# IntegroDiferencial_SCH.net
KiCad netlist of a schematic drawn in Altium Designer
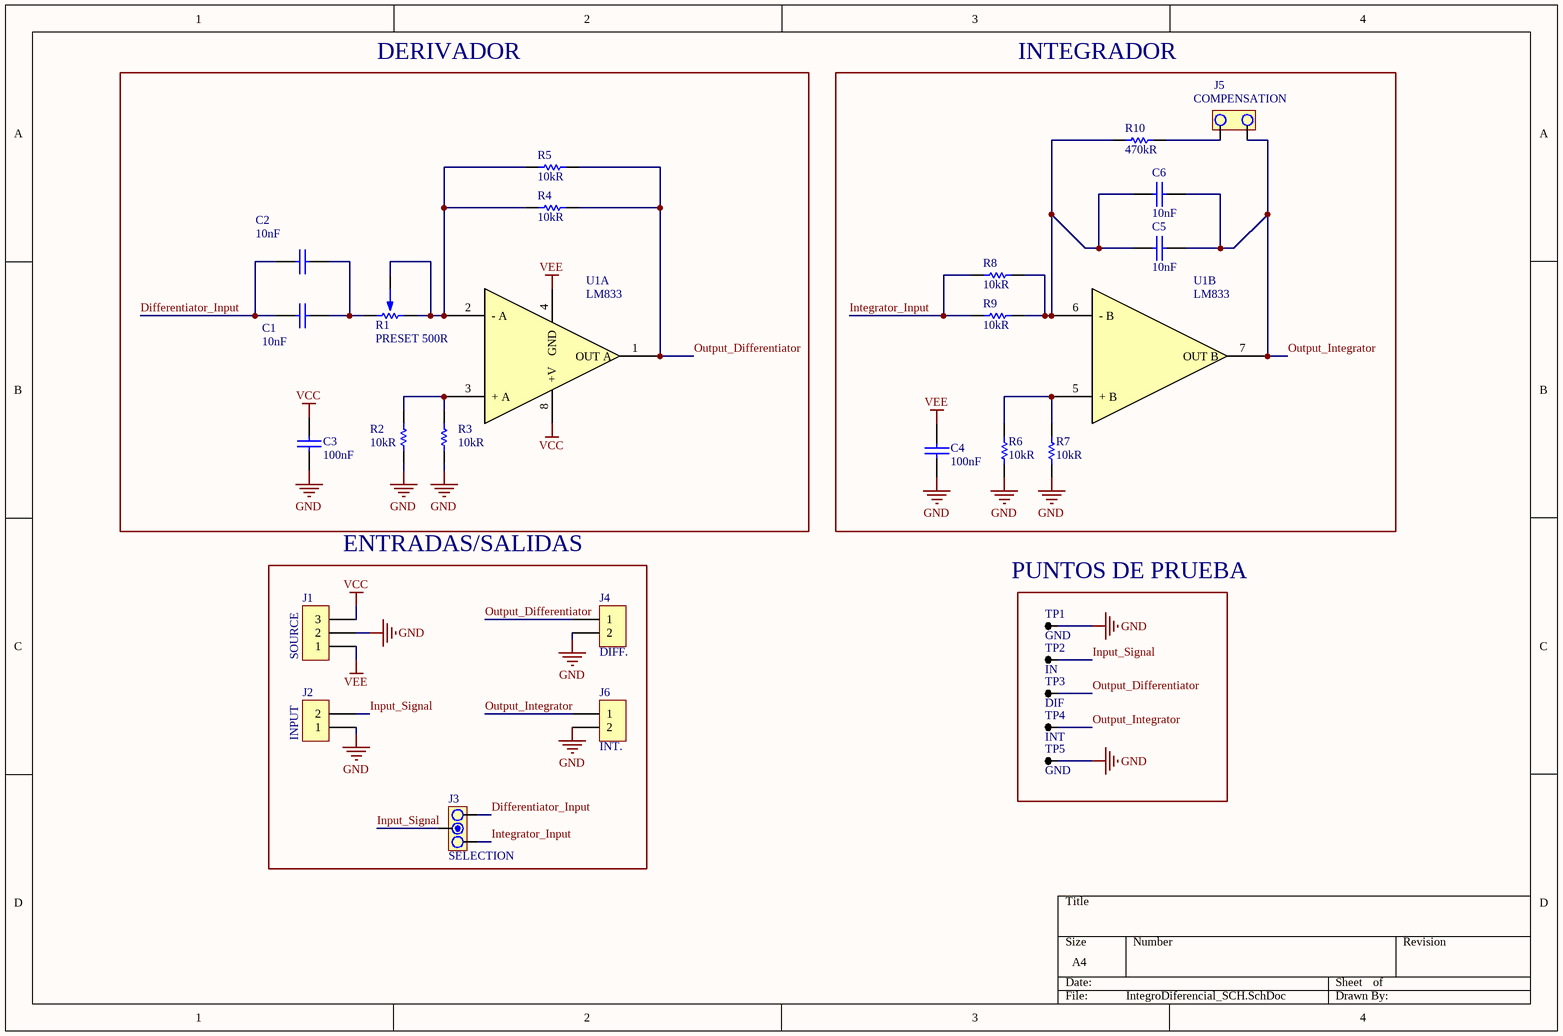
[diagram p0: IntegroDiferencial_SCH.SchDoc]

(export (version "E")
  (design (tool "Eeschema 10.0.6"))
  (components
    (comp (ref "C1")
      (value "10nF")
      (footprint "0805")
      (description "CAP 10nF 0805")
      (libsource (lib "LIBEBAL") (part "CAP"))
    )
    (comp (ref "C2")
      (value "10nF")
      (footprint "0805")
      (description "CAP 10nF 0805")
      (libsource (lib "LIBEBAL") (part "CAP"))
    )
    (comp (ref "C3")
      (value "100nF")
      (footprint "0805")
      (description "CAP 100nF 0805")
      (libsource (lib "LIBEBAL") (part "CAP"))
    )
    (comp (ref "C4")
      (value "100nF")
      (footprint "0805")
      (description "CAP 100nF 0805")
      (libsource (lib "LIBEBAL") (part "CAP"))
    )
    (comp (ref "C5")
      (value "10nF")
      (footprint "0805")
      (description "CAP 10nF 0805")
      (libsource (lib "LIBEBAL") (part "CAP"))
    )
    (comp (ref "C6")
      (value "10nF")
      (footprint "0805")
      (description "CAP 10nF 0805")
      (libsource (lib "LIBEBAL") (part "CAP"))
    )
    (comp (ref "J1")
      (value "SOURCE")
      (footprint "BORNERA3")
      (description "BORNERA 3")
      (libsource (lib "LIBEBAL") (part "BORNERA 3"))
    )
    (comp (ref "J2")
      (value "INPUT")
      (footprint "BORNERA2")
      (description "BORNERA 2")
      (libsource (lib "LIBEBAL") (part "BORNERA 2"))
    )
    (comp (ref "J3")
      (value "SELECTION")
      (footprint "JUMPER3")
      (description "JUMPER")
      (libsource (lib "LIBEBAL") (part "JUMPER3"))
    )
    (comp (ref "J4")
      (value "DIFF.")
      (footprint "BORNERA2")
      (description "BORNERA 2")
      (libsource (lib "") (part "BORNERA 2_1"))
    )
    (comp (ref "J5")
      (value "COMPENSATION")
      (footprint "JUMPER2")
      (description "JUMPER")
      (libsource (lib "LIBEBAL") (part "JUMPER"))
    )
    (comp (ref "J6")
      (value "INT.")
      (footprint "BORNERA2")
      (description "BORNERA 2")
      (libsource (lib "") (part "BORNERA 2_1"))
    )
    (comp (ref "R1") (value "PRESET 500R") (footprint "PRESET V") (libsource (lib "LIBEBAL") (part "PRESET")))
    (comp (ref "R2")
      (value "10kR")
      (footprint "0805")
      (description "RES 10kR 0805")
      (libsource (lib "LIBEBAL") (part "RES"))
    )
    (comp (ref "R3")
      (value "10kR")
      (footprint "0805")
      (description "RES 10kR 0805")
      (libsource (lib "LIBEBAL") (part "RES"))
    )
    (comp (ref "R4")
      (value "10kR")
      (footprint "0805")
      (description "RES 10kR 0805")
      (libsource (lib "LIBEBAL") (part "RES"))
    )
    (comp (ref "R5")
      (value "10kR")
      (footprint "0805")
      (description "RES 10kR 0805")
      (libsource (lib "LIBEBAL") (part "RES"))
    )
    (comp (ref "R6")
      (value "10kR")
      (footprint "0805")
      (description "RES 10kR 0805")
      (libsource (lib "LIBEBAL") (part "RES"))
    )
    (comp (ref "R7")
      (value "10kR")
      (footprint "0805")
      (description "RES 10kR 0805")
      (libsource (lib "LIBEBAL") (part "RES"))
    )
    (comp (ref "R8")
      (value "10kR")
      (footprint "0805")
      (description "RES 10kR 0805")
      (libsource (lib "LIBEBAL") (part "RES"))
    )
    (comp (ref "R9")
      (value "10kR")
      (footprint "0805")
      (description "RES 10kR 0805")
      (libsource (lib "LIBEBAL") (part "RES"))
    )
    (comp (ref "R10")
      (value "470kR")
      (footprint "0805")
      (description "RES 470kR 0805")
      (libsource (lib "LIBEBAL") (part "RES"))
    )
    (comp (ref "TP1")
      (value "GND")
      (footprint "TPTH")
      (description "TESTPOINT")
      (libsource (lib "LIBEBAL") (part "TP"))
    )
    (comp (ref "TP2")
      (value "IN")
      (footprint "TPTH")
      (description "TESTPOINT")
      (libsource (lib "LIBEBAL") (part "TP"))
    )
    (comp (ref "TP3")
      (value "DIF")
      (footprint "TPTH")
      (description "TESTPOINT")
      (libsource (lib "LIBEBAL") (part "TP"))
    )
    (comp (ref "TP4")
      (value "INT")
      (footprint "TPTH")
      (description "TESTPOINT")
      (libsource (lib "LIBEBAL") (part "TP"))
    )
    (comp (ref "TP5")
      (value "GND")
      (footprint "TPTH")
      (description "TESTPOINT")
      (libsource (lib "LIBEBAL") (part "TP"))
    )
    (comp (ref "U1")
      (value "LM833")
      (footprint "DIP8")
      (description "Dual Audio Operational Amplifier")
      (libsource (lib "LIBEBAL") (part "LM833"))
    )
  )
  (nets
    (net (code "1") (name "/Differentiator_Input") (class "Default")
      (node (ref "C1") (pin "1") (pinfunction "1_1") (pintype "passive"))
      (node (ref "C2") (pin "1") (pinfunction "1_1") (pintype "passive"))
      (node (ref "J3") (pin "1") (pinfunction "1_1") (pintype "passive"))
    )
    (net (code "2") (name "/Input_Signal") (class "Default")
      (node (ref "J2") (pin "2") (pinfunction "2_2") (pintype "passive"))
      (node (ref "J3") (pin "2") (pinfunction "2_2") (pintype "passive"))
      (node (ref "TP2") (pin "1") (pinfunction "1_1") (pintype "passive"))
    )
    (net (code "3") (name "/Integrator_Input") (class "Default")
      (node (ref "J3") (pin "3") (pinfunction "3_3") (pintype "passive"))
      (node (ref "R8") (pin "1") (pinfunction "1_1") (pintype "passive"))
      (node (ref "R9") (pin "1") (pinfunction "1_1") (pintype "passive"))
    )
    (net (code "4") (name "/Output_Differentiator") (class "Default")
      (node (ref "J4") (pin "1") (pinfunction "1_1") (pintype "passive"))
      (node (ref "R4") (pin "1") (pinfunction "1_1") (pintype "passive"))
      (node (ref "R5") (pin "1") (pinfunction "1_1") (pintype "passive"))
      (node (ref "TP3") (pin "1") (pinfunction "1_1") (pintype "passive"))
      (node (ref "U1") (pin "1") (pinfunction "OUT_A_1") (pintype "passive"))
    )
    (net (code "5") (name "/Output_Integrator") (class "Default")
      (node (ref "C5") (pin "1") (pinfunction "1_1") (pintype "passive"))
      (node (ref "C6") (pin "1") (pinfunction "1_1") (pintype "passive"))
      (node (ref "J5") (pin "1") (pinfunction "1_1") (pintype "passive"))
      (node (ref "J6") (pin "1") (pinfunction "1_1") (pintype "passive"))
      (node (ref "TP4") (pin "1") (pinfunction "1_1") (pintype "passive"))
      (node (ref "U1") (pin "7") (pinfunction "OUT_B_7") (pintype "passive"))
    )
    (net (code "6") (name "GND") (class "Default")
      (node (ref "C3") (pin "1") (pinfunction "1_1") (pintype "passive"))
      (node (ref "C4") (pin "1") (pinfunction "1_1") (pintype "passive"))
      (node (ref "J1") (pin "2") (pinfunction "2_2") (pintype "passive"))
      (node (ref "J2") (pin "1") (pinfunction "1_1") (pintype "passive"))
      (node (ref "J4") (pin "2") (pinfunction "2_2") (pintype "passive"))
      (node (ref "J6") (pin "2") (pinfunction "2_2") (pintype "passive"))
      (node (ref "R2") (pin "1") (pinfunction "1_1") (pintype "passive"))
      (node (ref "R3") (pin "1") (pinfunction "1_1") (pintype "passive"))
      (node (ref "R6") (pin "1") (pinfunction "1_1") (pintype "passive"))
      (node (ref "R7") (pin "1") (pinfunction "1_1") (pintype "passive"))
      (node (ref "TP1") (pin "1") (pinfunction "1_1") (pintype "passive"))
      (node (ref "TP5") (pin "1") (pinfunction "1_1") (pintype "passive"))
    )
    (net (code "7") (name "Net-(C1-Pad2)") (class "Default")
      (node (ref "C1") (pin "2") (pinfunction "2_2") (pintype "passive"))
      (node (ref "C2") (pin "2") (pinfunction "2_2") (pintype "passive"))
      (node (ref "R1") (pin "1") (pinfunction "1_1") (pintype "passive"))
    )
    (net (code "8") (name "Net-(J5-Pad2)") (class "Default")
      (node (ref "J5") (pin "2") (pinfunction "2_2") (pintype "passive"))
      (node (ref "R10") (pin "2") (pinfunction "2_2") (pintype "passive"))
    )
    (net (code "9") (name "Net-(U1A-+_A)") (class "Default")
      (node (ref "R2") (pin "2") (pinfunction "2_2") (pintype "passive"))
      (node (ref "R3") (pin "2") (pinfunction "2_2") (pintype "passive"))
      (node (ref "U1") (pin "3") (pinfunction "+_A_3") (pintype "passive"))
    )
    (net (code "10") (name "Net-(U1A--_A)") (class "Default")
      (node (ref "R1") (pin "2") (pinfunction "2_2") (pintype "passive"))
      (node (ref "R1") (pin "3") (pinfunction "3_3") (pintype "passive"))
      (node (ref "R4") (pin "2") (pinfunction "2_2") (pintype "passive"))
      (node (ref "R5") (pin "2") (pinfunction "2_2") (pintype "passive"))
      (node (ref "U1") (pin "2") (pinfunction "-_A_2") (pintype "passive"))
    )
    (net (code "11") (name "Net-(U1B-+_B)") (class "Default")
      (node (ref "R6") (pin "2") (pinfunction "2_2") (pintype "passive"))
      (node (ref "R7") (pin "2") (pinfunction "2_2") (pintype "passive"))
      (node (ref "U1") (pin "5") (pinfunction "+_B_5") (pintype "passive"))
    )
    (net (code "12") (name "Net-(U1B--_B)") (class "Default")
      (node (ref "C5") (pin "2") (pinfunction "2_2") (pintype "passive"))
      (node (ref "C6") (pin "2") (pinfunction "2_2") (pintype "passive"))
      (node (ref "R10") (pin "1") (pinfunction "1_1") (pintype "passive"))
      (node (ref "R8") (pin "2") (pinfunction "2_2") (pintype "passive"))
      (node (ref "R9") (pin "2") (pinfunction "2_2") (pintype "passive"))
      (node (ref "U1") (pin "6") (pinfunction "-_B_6") (pintype "passive"))
    )
    (net (code "13") (name "VCC") (class "Default")
      (node (ref "C3") (pin "2") (pinfunction "2_2") (pintype "passive"))
      (node (ref "J1") (pin "3") (pinfunction "3_3") (pintype "passive"))
      (node (ref "U1") (pin "8") (pinfunction "+V_8") (pintype "passive"))
    )
    (net (code "14") (name "VEE") (class "Default")
      (node (ref "C4") (pin "2") (pinfunction "2_2") (pintype "passive"))
      (node (ref "J1") (pin "1") (pinfunction "1_1") (pintype "passive"))
      (node (ref "U1") (pin "4") (pinfunction "GND_4") (pintype "passive"))
    )
  )
)
